# ESPSensorBoard.net
KiCad netlist of a schematic drawn in EAGLE
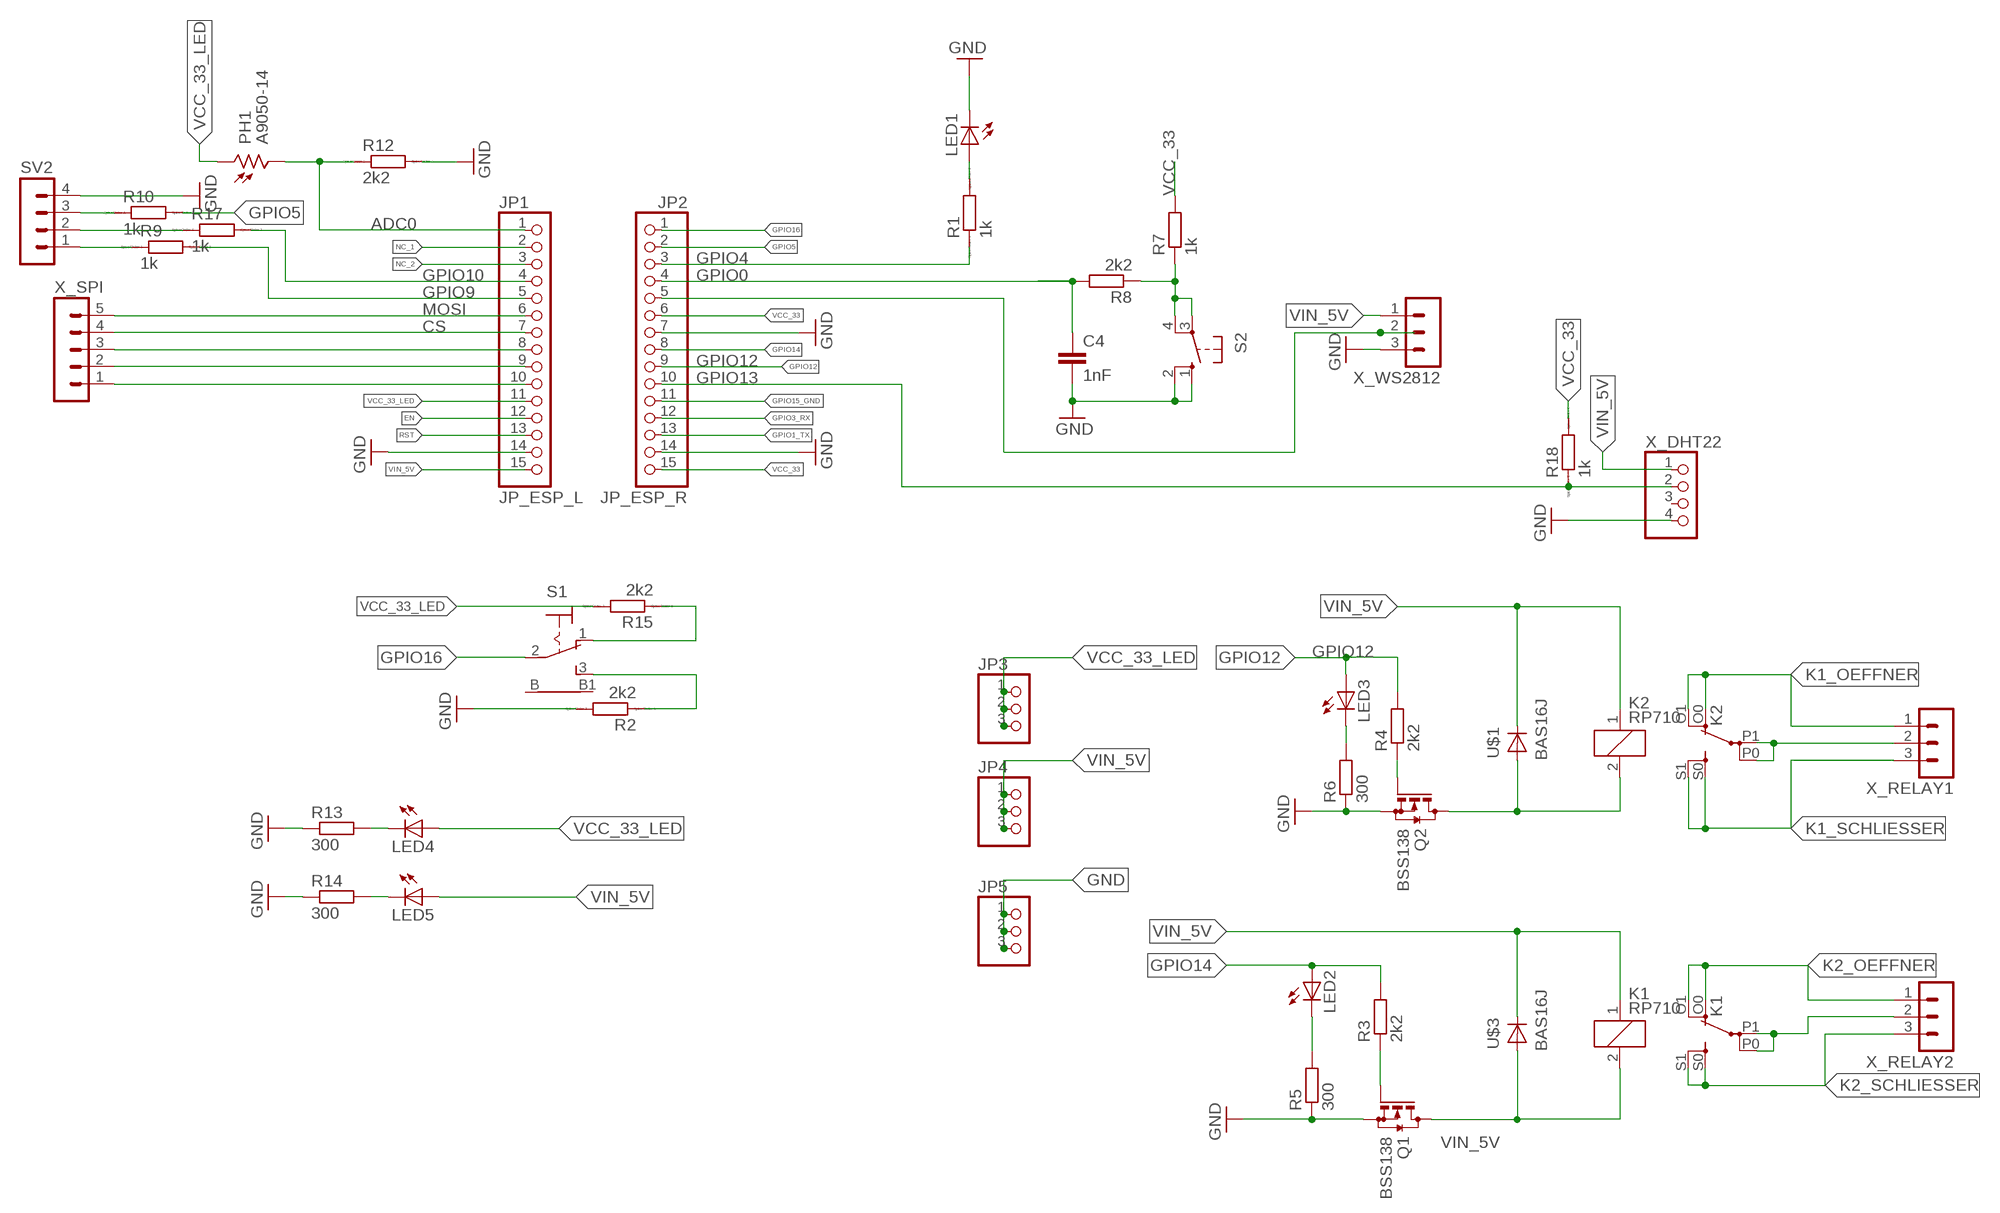
[diagram p0: schematic, sheet 1]

(export (version "E")
  (design (tool "Eeschema 10.0.6"))
  (components
    (comp (ref "C4")
      (value "1nF")
      (footprint "eagle-import:C0805K")
      (libsource (lib "eagle-import") (part "C-EUC0805K"))
    )
    (comp (ref "JP1")
      (value "JP_ESP_L")
      (footprint "eagle-import:1X15")
      (libsource (lib "eagle-import") (part "PINHD-1X15"))
    )
    (comp (ref "JP2")
      (value "JP_ESP_R")
      (footprint "eagle-import:1X15")
      (libsource (lib "eagle-import") (part "PINHD-1X15"))
    )
    (comp (ref "JP3")
      (value "PINHD-1X3")
      (footprint "eagle-import:1X03")
      (libsource (lib "eagle-import") (part "PINHD-1X3"))
    )
    (comp (ref "JP4")
      (value "PINHD-1X3")
      (footprint "eagle-import:1X03")
      (libsource (lib "eagle-import") (part "PINHD-1X3"))
    )
    (comp (ref "JP5")
      (value "PINHD-1X3")
      (footprint "eagle-import:1X03")
      (libsource (lib "eagle-import") (part "PINHD-1X3"))
    )
    (comp (ref "K1")
      (value "RP710")
      (footprint "eagle-import:RP710")
      (fields (field (name "MF") "TYCO ELECTRONICS") (field (name "MPN") "RP710024"))
      (libsource (lib "eagle-import") (part "RP710"))
    )
    (comp (ref "K2")
      (value "RP710")
      (footprint "eagle-import:RP710")
      (fields (field (name "MF") "TYCO ELECTRONICS") (field (name "MPN") "RP710024"))
      (libsource (lib "eagle-import") (part "RP710"))
    )
    (comp (ref "LED1")
      (value "LED5MM")
      (footprint "eagle-import:LED5MM")
      (libsource (lib "eagle-import") (part "LED5MM"))
    )
    (comp (ref "LED2")
      (value "LED3MM")
      (footprint "eagle-import:LED3MM")
      (libsource (lib "eagle-import") (part "LED3MM"))
    )
    (comp (ref "LED3")
      (value "LED3MM")
      (footprint "eagle-import:LED3MM")
      (libsource (lib "eagle-import") (part "LED3MM"))
    )
    (comp (ref "LED4")
      (value "LED3MM")
      (footprint "eagle-import:LED3MM")
      (libsource (lib "eagle-import") (part "LED3MM"))
    )
    (comp (ref "LED5")
      (value "LED3MM")
      (footprint "eagle-import:LED3MM")
      (libsource (lib "eagle-import") (part "LED3MM"))
    )
    (comp (ref "PH1")
      (value "A9050-14")
      (footprint "eagle-import:M9960")
      (libsource (lib "eagle-import") (part "M9960_11A"))
    )
    (comp (ref "Q1")
      (value "BSS138")
      (footprint "eagle-import:SOT23")
      (libsource (lib "eagle-import") (part "BSS123"))
    )
    (comp (ref "Q2")
      (value "BSS138")
      (footprint "eagle-import:SOT23")
      (libsource (lib "eagle-import") (part "BSS123"))
    )
    (comp (ref "R1")
      (value "1k")
      (footprint "eagle-import:R0805")
      (libsource (lib "eagle-import") (part "R"))
    )
    (comp (ref "R2")
      (value "2k2")
      (footprint "eagle-import:R0805")
      (libsource (lib "eagle-import") (part "R"))
    )
    (comp (ref "R3")
      (value "2k2")
      (footprint "eagle-import:R0805")
      (libsource (lib "eagle-import") (part "R-EU_R0805"))
    )
    (comp (ref "R4")
      (value "2k2")
      (footprint "eagle-import:R0805")
      (libsource (lib "eagle-import") (part "R-EU_R0805"))
    )
    (comp (ref "R5")
      (value "300")
      (footprint "eagle-import:R0805")
      (libsource (lib "eagle-import") (part "R-EU_R0805"))
    )
    (comp (ref "R6")
      (value "300")
      (footprint "eagle-import:R0805")
      (libsource (lib "eagle-import") (part "R-EU_R0805"))
    )
    (comp (ref "R7")
      (value "1k")
      (footprint "eagle-import:R0805")
      (libsource (lib "eagle-import") (part "R-EU_R0805"))
    )
    (comp (ref "R8")
      (value "2k2")
      (footprint "eagle-import:R0805")
      (libsource (lib "eagle-import") (part "R-EU_R0805"))
    )
    (comp (ref "R9")
      (value "1k")
      (footprint "eagle-import:R0805")
      (libsource (lib "eagle-import") (part "R"))
    )
    (comp (ref "R10")
      (value "1k")
      (footprint "eagle-import:R0805")
      (libsource (lib "eagle-import") (part "R"))
    )
    (comp (ref "R12")
      (value "2k2")
      (footprint "eagle-import:R0805")
      (libsource (lib "eagle-import") (part "R"))
    )
    (comp (ref "R13")
      (value "300")
      (footprint "eagle-import:R0805")
      (libsource (lib "eagle-import") (part "R-EU_R0805"))
    )
    (comp (ref "R14")
      (value "300")
      (footprint "eagle-import:R0805")
      (libsource (lib "eagle-import") (part "R-EU_R0805"))
    )
    (comp (ref "R15")
      (value "2k2")
      (footprint "eagle-import:R0805")
      (libsource (lib "eagle-import") (part "R"))
    )
    (comp (ref "R17")
      (value "1k")
      (footprint "eagle-import:R0805")
      (libsource (lib "eagle-import") (part "R"))
    )
    (comp (ref "R18")
      (value "1k")
      (footprint "eagle-import:R0805")
      (libsource (lib "eagle-import") (part "R"))
    )
    (comp (ref "S1")
      (value "LPV-1")
      (footprint "eagle-import:LPV-1")
      (libsource (lib "eagle-import") (part "LPV-1"))
    )
    (comp (ref "S2")
      (value "10-XX")
      (footprint "eagle-import:B3F-10XX")
      (fields (field (name "MPN") "B3F-1000"))
      (libsource (lib "eagle-import") (part "10-XX"))
    )
    (comp (ref "SV2")
      (value "MA04-1")
      (footprint "eagle-import:MA04-1")
      (libsource (lib "eagle-import") (part "MA04-1"))
    )
    (comp (ref "U$1")
      (value "BAS16J")
      (footprint "eagle-import:0805-POL")
      (libsource (lib "eagle-import") (part "BAS16J"))
    )
    (comp (ref "U$3")
      (value "BAS16J")
      (footprint "eagle-import:0805-POL")
      (libsource (lib "eagle-import") (part "BAS16J"))
    )
    (comp (ref "X_DHT22")
      (value "PINHD-1X4")
      (footprint "eagle-import:1X04")
      (libsource (lib "eagle-import") (part "PINHD-1X4"))
    )
    (comp (ref "X_RELAY1")
      (value "MA03-1")
      (footprint "eagle-import:MA03-1")
      (libsource (lib "eagle-import") (part "MA03-1"))
    )
    (comp (ref "X_RELAY2")
      (value "MA03-1")
      (footprint "eagle-import:MA03-1")
      (libsource (lib "eagle-import") (part "MA03-1"))
    )
    (comp (ref "X_SPI")
      (value "MA05-1")
      (footprint "eagle-import:MA05-1")
      (libsource (lib "eagle-import") (part "MA05-1"))
    )
    (comp (ref "X_WS2812")
      (value "MA03-1")
      (footprint "eagle-import:MA03-1")
      (libsource (lib "eagle-import") (part "MA03-1"))
    )
  )
  (nets
    (net (code "1") (name "/ADC0") (class "Default")
      (node (ref "JP1") (pin "1") (pinfunction "1_1") (pintype "passive"))
      (node (ref "PH1") (pin "2") (pinfunction "2_2") (pintype "passive"))
      (node (ref "R12") (pin "1") (pinfunction "1_1") (pintype "passive"))
    )
    (net (code "2") (name "/CS") (class "Default")
      (node (ref "JP1") (pin "7") (pinfunction "7_7") (pintype "passive"))
      (node (ref "X_SPI") (pin "4") (pinfunction "4_4") (pintype "passive"))
    )
    (net (code "3") (name "/GPIO0") (class "Default")
      (node (ref "C4") (pin "1") (pinfunction "1_1") (pintype "passive"))
      (node (ref "JP2") (pin "4") (pinfunction "4_4") (pintype "passive"))
      (node (ref "R8") (pin "2") (pinfunction "2_2") (pintype "passive"))
    )
    (net (code "4") (name "/GPIO4") (class "Default")
      (node (ref "JP2") (pin "3") (pinfunction "3_3") (pintype "passive"))
      (node (ref "R1") (pin "1") (pinfunction "1_1") (pintype "passive"))
    )
    (net (code "5") (name "/GPIO9") (class "Default")
      (node (ref "JP1") (pin "5") (pinfunction "5_5") (pintype "passive"))
      (node (ref "R9") (pin "2") (pinfunction "2_2") (pintype "passive"))
    )
    (net (code "6") (name "/GPIO10") (class "Default")
      (node (ref "JP1") (pin "4") (pinfunction "4_4") (pintype "passive"))
      (node (ref "R17") (pin "2") (pinfunction "2_2") (pintype "passive"))
    )
    (net (code "7") (name "/GPIO13") (class "Default")
      (node (ref "JP2") (pin "10") (pinfunction "10_10") (pintype "passive"))
      (node (ref "R18") (pin "1") (pinfunction "1_1") (pintype "passive"))
      (node (ref "X_DHT22") (pin "2") (pinfunction "2_2") (pintype "passive"))
    )
    (net (code "8") (name "/MOSI") (class "Default")
      (node (ref "JP1") (pin "6") (pinfunction "6_6") (pintype "passive"))
      (node (ref "X_SPI") (pin "5") (pinfunction "5_5") (pintype "passive"))
    )
    (net (code "9") (name "EN") (class "Default")
      (node (ref "JP1") (pin "12") (pinfunction "12_12") (pintype "passive"))
    )
    (net (code "10") (name "GND") (class "Default")
      (node (ref "C4") (pin "2") (pinfunction "2_2") (pintype "passive"))
      (node (ref "JP1") (pin "14") (pinfunction "14_14") (pintype "passive"))
      (node (ref "JP2") (pin "14") (pinfunction "14_14") (pintype "passive"))
      (node (ref "JP2") (pin "7") (pinfunction "7_7") (pintype "passive"))
      (node (ref "JP5") (pin "1") (pinfunction "1_1") (pintype "passive"))
      (node (ref "JP5") (pin "2") (pinfunction "2_2") (pintype "passive"))
      (node (ref "JP5") (pin "3") (pinfunction "3_3") (pintype "passive"))
      (node (ref "LED1") (pin "K") (pinfunction "C_K") (pintype "passive"))
      (node (ref "Q1") (pin "2") (pinfunction "S_2") (pintype "passive"))
      (node (ref "Q2") (pin "2") (pinfunction "S_2") (pintype "passive"))
      (node (ref "R12") (pin "2") (pinfunction "2_2") (pintype "passive"))
      (node (ref "R13") (pin "1") (pinfunction "1_1") (pintype "passive"))
      (node (ref "R14") (pin "1") (pinfunction "1_1") (pintype "passive"))
      (node (ref "R2") (pin "2") (pinfunction "2_2") (pintype "passive"))
      (node (ref "R5") (pin "1") (pinfunction "1_1") (pintype "passive"))
      (node (ref "R6") (pin "1") (pinfunction "1_1") (pintype "passive"))
      (node (ref "S2") (pin "1") (pinfunction "S_1") (pintype "passive"))
      (node (ref "S2") (pin "2") (pinfunction "S1_2") (pintype "passive"))
      (node (ref "SV2") (pin "4") (pinfunction "4_4") (pintype "passive"))
      (node (ref "X_DHT22") (pin "4") (pinfunction "4_4") (pintype "passive"))
      (node (ref "X_WS2812") (pin "3") (pinfunction "3_3") (pintype "passive"))
    )
    (net (code "11") (name "GPIO1_TX") (class "Default")
      (node (ref "JP2") (pin "13") (pinfunction "13_13") (pintype "passive"))
    )
    (net (code "12") (name "GPIO3_RX") (class "Default")
      (node (ref "JP2") (pin "12") (pinfunction "12_12") (pintype "passive"))
    )
    (net (code "13") (name "GPIO5") (class "Default")
      (node (ref "JP2") (pin "2") (pinfunction "2_2") (pintype "passive"))
      (node (ref "R10") (pin "2") (pinfunction "2_2") (pintype "passive"))
    )
    (net (code "14") (name "GPIO12") (class "Default")
      (node (ref "JP2") (pin "9") (pinfunction "9_9") (pintype "passive"))
      (node (ref "LED3") (pin "A") (pinfunction "A_A") (pintype "passive"))
      (node (ref "R4") (pin "2") (pinfunction "2_2") (pintype "passive"))
    )
    (net (code "15") (name "GPIO14") (class "Default")
      (node (ref "JP2") (pin "8") (pinfunction "8_8") (pintype "passive"))
      (node (ref "LED2") (pin "A") (pinfunction "A_A") (pintype "passive"))
      (node (ref "R3") (pin "2") (pinfunction "2_2") (pintype "passive"))
    )
    (net (code "16") (name "GPIO15_GND") (class "Default")
      (node (ref "JP2") (pin "11") (pinfunction "11_11") (pintype "passive"))
    )
    (net (code "17") (name "GPIO16") (class "Default")
      (node (ref "JP2") (pin "1") (pinfunction "1_1") (pintype "passive"))
      (node (ref "S1") (pin "2") (pinfunction "P_2") (pintype "passive"))
    )
    (net (code "18") (name "K1_OEFFNER") (class "Default")
      (node (ref "K2") (pin "O0") (pinfunction "O_O0") (pintype "passive"))
      (node (ref "K2") (pin "O1") (pinfunction "O_O1") (pintype "passive"))
      (node (ref "X_RELAY1") (pin "1") (pinfunction "1_1") (pintype "passive"))
    )
    (net (code "19") (name "K1_SCHLIESSER") (class "Default")
      (node (ref "K2") (pin "S0") (pinfunction "S_S0") (pintype "passive"))
      (node (ref "K2") (pin "S1") (pinfunction "S_S1") (pintype "passive"))
      (node (ref "X_RELAY1") (pin "3") (pinfunction "3_3") (pintype "passive"))
    )
    (net (code "20") (name "K2_OEFFNER") (class "Default")
      (node (ref "K1") (pin "O0") (pinfunction "O_O0") (pintype "passive"))
      (node (ref "K1") (pin "O1") (pinfunction "O_O1") (pintype "passive"))
      (node (ref "X_RELAY2") (pin "1") (pinfunction "1_1") (pintype "passive"))
    )
    (net (code "21") (name "K2_SCHLIESSER") (class "Default")
      (node (ref "K1") (pin "S0") (pinfunction "S_S0") (pintype "passive"))
      (node (ref "K1") (pin "S1") (pinfunction "S_S1") (pintype "passive"))
      (node (ref "X_RELAY2") (pin "3") (pinfunction "3_3") (pintype "passive"))
    )
    (net (code "22") (name "NC_1") (class "Default")
      (node (ref "JP1") (pin "2") (pinfunction "2_2") (pintype "passive"))
    )
    (net (code "23") (name "NC_2") (class "Default")
      (node (ref "JP1") (pin "3") (pinfunction "3_3") (pintype "passive"))
    )
    (net (code "24") (name "Net-(JP1-Pad8)") (class "Default")
      (node (ref "JP1") (pin "8") (pinfunction "8_8") (pintype "passive"))
      (node (ref "X_SPI") (pin "3") (pinfunction "3_3") (pintype "passive"))
    )
    (net (code "25") (name "Net-(JP1-Pad9)") (class "Default")
      (node (ref "JP1") (pin "9") (pinfunction "9_9") (pintype "passive"))
      (node (ref "X_SPI") (pin "2") (pinfunction "2_2") (pintype "passive"))
    )
    (net (code "26") (name "Net-(JP1-Pad10)") (class "Default")
      (node (ref "JP1") (pin "10") (pinfunction "10_10") (pintype "passive"))
      (node (ref "X_SPI") (pin "1") (pinfunction "1_1") (pintype "passive"))
    )
    (net (code "27") (name "Net-(JP2-Pad5)") (class "Default")
      (node (ref "JP2") (pin "5") (pinfunction "5_5") (pintype "passive"))
      (node (ref "X_WS2812") (pin "2") (pinfunction "2_2") (pintype "passive"))
    )
    (net (code "28") (name "Net-(K1B-P-PadP0)") (class "Default")
      (node (ref "K1") (pin "P0") (pinfunction "P_P0") (pintype "passive"))
      (node (ref "K1") (pin "P1") (pinfunction "P_P1") (pintype "passive"))
      (node (ref "X_RELAY2") (pin "2") (pinfunction "2_2") (pintype "passive"))
    )
    (net (code "29") (name "Net-(K2B-P-PadP0)") (class "Default")
      (node (ref "K2") (pin "P0") (pinfunction "P_P0") (pintype "passive"))
      (node (ref "K2") (pin "P1") (pinfunction "P_P1") (pintype "passive"))
      (node (ref "X_RELAY1") (pin "2") (pinfunction "2_2") (pintype "passive"))
    )
    (net (code "30") (name "Net-(LED1-PadA)") (class "Default")
      (node (ref "LED1") (pin "A") (pinfunction "A_A") (pintype "passive"))
      (node (ref "R1") (pin "2") (pinfunction "2_2") (pintype "passive"))
    )
    (net (code "31") (name "Net-(LED2-C)") (class "Default")
      (node (ref "LED2") (pin "K") (pinfunction "C_K") (pintype "passive"))
      (node (ref "R5") (pin "2") (pinfunction "2_2") (pintype "passive"))
    )
    (net (code "32") (name "Net-(LED3-C)") (class "Default")
      (node (ref "LED3") (pin "K") (pinfunction "C_K") (pintype "passive"))
      (node (ref "R6") (pin "2") (pinfunction "2_2") (pintype "passive"))
    )
    (net (code "33") (name "Net-(LED4-C)") (class "Default")
      (node (ref "LED4") (pin "K") (pinfunction "C_K") (pintype "passive"))
      (node (ref "R13") (pin "2") (pinfunction "2_2") (pintype "passive"))
    )
    (net (code "34") (name "Net-(LED5-C)") (class "Default")
      (node (ref "LED5") (pin "K") (pinfunction "C_K") (pintype "passive"))
      (node (ref "R14") (pin "2") (pinfunction "2_2") (pintype "passive"))
    )
    (net (code "35") (name "Net-(Q1-D)") (class "Default")
      (node (ref "K1") (pin "2") (pinfunction "2_2") (pintype "passive"))
      (node (ref "Q1") (pin "3") (pinfunction "D_3") (pintype "passive"))
      (node (ref "U$3") (pin "A") (pinfunction "A_A") (pintype "passive"))
    )
    (net (code "36") (name "Net-(Q1-G)") (class "Default")
      (node (ref "Q1") (pin "1") (pinfunction "G_1") (pintype "passive"))
      (node (ref "R3") (pin "1") (pinfunction "1_1") (pintype "passive"))
    )
    (net (code "37") (name "Net-(Q2-D)") (class "Default")
      (node (ref "K2") (pin "2") (pinfunction "2_2") (pintype "passive"))
      (node (ref "Q2") (pin "3") (pinfunction "D_3") (pintype "passive"))
      (node (ref "U$1") (pin "A") (pinfunction "A_A") (pintype "passive"))
    )
    (net (code "38") (name "Net-(Q2-G)") (class "Default")
      (node (ref "Q2") (pin "1") (pinfunction "G_1") (pintype "passive"))
      (node (ref "R4") (pin "1") (pinfunction "1_1") (pintype "passive"))
    )
    (net (code "39") (name "Net-(R9-Pad1)") (class "Default")
      (node (ref "R9") (pin "1") (pinfunction "1_1") (pintype "passive"))
      (node (ref "SV2") (pin "1") (pinfunction "1_1") (pintype "passive"))
    )
    (net (code "40") (name "Net-(R10-Pad1)") (class "Default")
      (node (ref "R10") (pin "1") (pinfunction "1_1") (pintype "passive"))
      (node (ref "SV2") (pin "3") (pinfunction "3_3") (pintype "passive"))
    )
    (net (code "41") (name "Net-(R17-Pad1)") (class "Default")
      (node (ref "R17") (pin "1") (pinfunction "1_1") (pintype "passive"))
      (node (ref "SV2") (pin "2") (pinfunction "2_2") (pintype "passive"))
    )
    (net (code "42") (name "Net-(S1-O)") (class "Default")
      (node (ref "R15") (pin "1") (pinfunction "1_1") (pintype "passive"))
      (node (ref "S1") (pin "1") (pinfunction "O_1") (pintype "passive"))
    )
    (net (code "43") (name "Net-(S1-S)") (class "Default")
      (node (ref "R2") (pin "1") (pinfunction "1_1") (pintype "passive"))
      (node (ref "S1") (pin "3") (pinfunction "S_3") (pintype "passive"))
    )
    (net (code "44") (name "Net-(S2-P)") (class "Default")
      (node (ref "R7") (pin "1") (pinfunction "1_1") (pintype "passive"))
      (node (ref "R8") (pin "1") (pinfunction "1_1") (pintype "passive"))
      (node (ref "S2") (pin "3") (pinfunction "P_3") (pintype "passive"))
      (node (ref "S2") (pin "4") (pinfunction "P1_4") (pintype "passive"))
    )
    (net (code "45") (name "RST") (class "Default")
      (node (ref "JP1") (pin "13") (pinfunction "13_13") (pintype "passive"))
    )
    (net (code "46") (name "VCC_33") (class "Default")
      (node (ref "JP2") (pin "15") (pinfunction "15_15") (pintype "passive"))
      (node (ref "JP2") (pin "6") (pinfunction "6_6") (pintype "passive"))
      (node (ref "R18") (pin "2") (pinfunction "2_2") (pintype "passive"))
      (node (ref "R7") (pin "2") (pinfunction "2_2") (pintype "passive"))
    )
    (net (code "47") (name "VCC_33_LED") (class "Default")
      (node (ref "JP1") (pin "11") (pinfunction "11_11") (pintype "passive"))
      (node (ref "JP3") (pin "1") (pinfunction "1_1") (pintype "passive"))
      (node (ref "JP3") (pin "2") (pinfunction "2_2") (pintype "passive"))
      (node (ref "JP3") (pin "3") (pinfunction "3_3") (pintype "passive"))
      (node (ref "LED4") (pin "A") (pinfunction "A_A") (pintype "passive"))
      (node (ref "PH1") (pin "1") (pinfunction "1_1") (pintype "passive"))
      (node (ref "R15") (pin "2") (pinfunction "2_2") (pintype "passive"))
    )
    (net (code "48") (name "VIN_5V") (class "Default")
      (node (ref "JP1") (pin "15") (pinfunction "15_15") (pintype "passive"))
      (node (ref "JP4") (pin "1") (pinfunction "1_1") (pintype "passive"))
      (node (ref "JP4") (pin "2") (pinfunction "2_2") (pintype "passive"))
      (node (ref "JP4") (pin "3") (pinfunction "3_3") (pintype "passive"))
      (node (ref "K1") (pin "1") (pinfunction "1_1") (pintype "passive"))
      (node (ref "K2") (pin "1") (pinfunction "1_1") (pintype "passive"))
      (node (ref "LED5") (pin "A") (pinfunction "A_A") (pintype "passive"))
      (node (ref "U$1") (pin "K") (pinfunction "C_K") (pintype "passive"))
      (node (ref "U$3") (pin "K") (pinfunction "C_K") (pintype "passive"))
      (node (ref "X_DHT22") (pin "1") (pinfunction "1_1") (pintype "passive"))
      (node (ref "X_WS2812") (pin "1") (pinfunction "1_1") (pintype "passive"))
    )
    (net (code "49") (name "unconnected-(S1-PadB)") (class "Default")
      (node (ref "S1") (pin "B") (pinfunction "B_B") (pintype "passive"))
    )
    (net (code "50") (name "unconnected-(S1-PadB1)") (class "Default")
      (node (ref "S1") (pin "B1") (pinfunction "B1_B1") (pintype "passive"))
    )
    (net (code "51") (name "unconnected-(X_DHT22-Pad3)") (class "Default")
      (node (ref "X_DHT22") (pin "3") (pinfunction "3_3") (pintype "passive"))
    )
  )
)
